# RocketWatch-BOTTOM.net
KiCad netlist of a schematic drawn in EAGLE
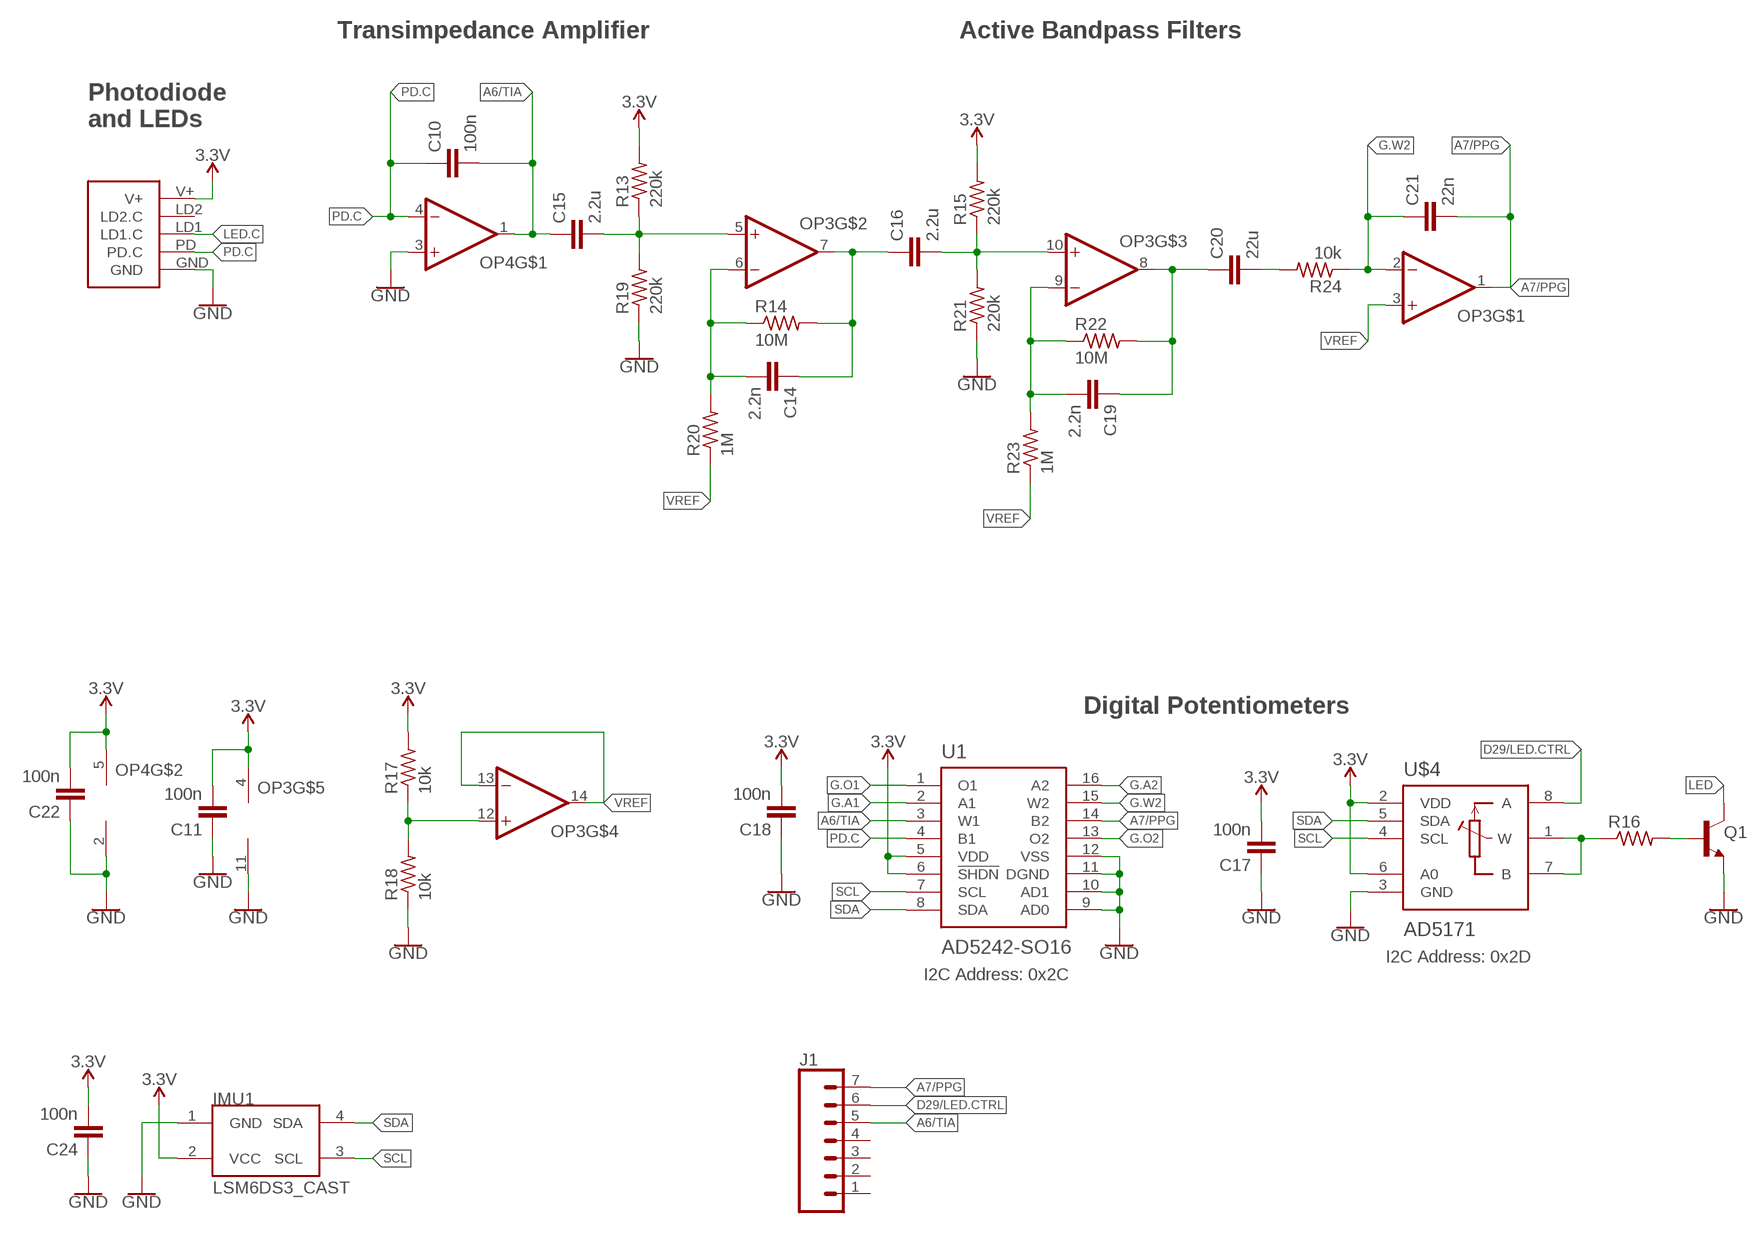
[diagram p0: schematic, sheet 1]

(export (version "E")
  (design (tool "Eeschema 10.0.6"))
  (components
    (comp (ref "C10")
      (value "100n")
      (footprint "eagle-import:C0603")
      (libsource (lib "eagle-import") (part "CAPACITOR0603"))
    )
    (comp (ref "C11")
      (value "100n")
      (footprint "eagle-import:C0603")
      (libsource (lib "eagle-import") (part "CAPACITOR0603"))
    )
    (comp (ref "C14")
      (value "2.2n")
      (footprint "eagle-import:C0603")
      (libsource (lib "eagle-import") (part "CAPACITOR0603"))
    )
    (comp (ref "C15")
      (value "2.2u")
      (footprint "eagle-import:C0603")
      (libsource (lib "eagle-import") (part "CAPACITOR0603"))
    )
    (comp (ref "C16")
      (value "2.2u")
      (footprint "eagle-import:C0603")
      (libsource (lib "eagle-import") (part "CAPACITOR0603"))
    )
    (comp (ref "C17")
      (value "100n")
      (footprint "eagle-import:C0603")
      (libsource (lib "eagle-import") (part "CAPACITOR0603"))
    )
    (comp (ref "C18")
      (value "100n")
      (footprint "eagle-import:C0603")
      (libsource (lib "eagle-import") (part "CAPACITOR0603"))
    )
    (comp (ref "C19")
      (value "2.2n")
      (footprint "eagle-import:C0603")
      (libsource (lib "eagle-import") (part "CAPACITOR0603"))
    )
    (comp (ref "C20")
      (value "22u")
      (footprint "eagle-import:C0603")
      (libsource (lib "eagle-import") (part "CAPACITOR0603"))
    )
    (comp (ref "C21")
      (value "22n")
      (footprint "eagle-import:C0603")
      (libsource (lib "eagle-import") (part "CAPACITOR0603"))
    )
    (comp (ref "C22")
      (value "100n")
      (footprint "eagle-import:C0603")
      (libsource (lib "eagle-import") (part "CAPACITOR0603"))
    )
    (comp (ref "C24")
      (value "100n")
      (footprint "eagle-import:C0603")
      (libsource (lib "eagle-import") (part "CAPACITOR0603"))
    )
    (comp (ref "IMU1")
      (value "LSM6DS3_CAST")
      (footprint "eagle-import:LSM6DS3_CAST")
      (libsource (lib "eagle-import") (part "LSM6DS3_CAST"))
    )
    (comp (ref "J1")
      (value "CONN_07")
      (footprint "eagle-import:1X07")
      (libsource (lib "eagle-import") (part "CONN_07"))
    )
    (comp (ref "OP3")
      (value "OP-QUAD-SO14")
      (footprint "eagle-import:SO14")
      (libsource (lib "eagle-import") (part "OP-QUAD-SO14"))
    )
    (comp (ref "OP4")
      (value "OP-SINGLEOT")
      (footprint "eagle-import:SOT23-5")
      (libsource (lib "eagle-import") (part "OP-SINGLEOT"))
    )
    (comp (ref "Q1")
      (value "NPN-GENERIC")
      (footprint "eagle-import:SOT23-3")
      (libsource (lib "eagle-import") (part "NPN-GENERIC"))
    )
    (comp (ref "R13")
      (value "220k")
      (footprint "eagle-import:R0603")
      (libsource (lib "eagle-import") (part "RESISTOR0603"))
    )
    (comp (ref "R14")
      (value "10M")
      (footprint "eagle-import:R0603")
      (libsource (lib "eagle-import") (part "RESISTOR0603"))
    )
    (comp (ref "R15")
      (value "220k")
      (footprint "eagle-import:R0603")
      (libsource (lib "eagle-import") (part "RESISTOR0603"))
    )
    (comp (ref "R16")
      (value "RESISTOR0603")
      (footprint "eagle-import:R0603")
      (libsource (lib "eagle-import") (part "RESISTOR0603"))
    )
    (comp (ref "R17")
      (value "10k")
      (footprint "eagle-import:R0402")
      (libsource (lib "eagle-import") (part "RESISTOR0402"))
    )
    (comp (ref "R18")
      (value "10k")
      (footprint "eagle-import:R0402")
      (libsource (lib "eagle-import") (part "RESISTOR0402"))
    )
    (comp (ref "R19")
      (value "220k")
      (footprint "eagle-import:R0603")
      (libsource (lib "eagle-import") (part "RESISTOR0603"))
    )
    (comp (ref "R20")
      (value "1M")
      (footprint "eagle-import:R0603")
      (libsource (lib "eagle-import") (part "RESISTOR0603"))
    )
    (comp (ref "R21")
      (value "220k")
      (footprint "eagle-import:R0603")
      (libsource (lib "eagle-import") (part "RESISTOR0603"))
    )
    (comp (ref "R22")
      (value "10M")
      (footprint "eagle-import:R0603")
      (libsource (lib "eagle-import") (part "RESISTOR0603"))
    )
    (comp (ref "R23")
      (value "1M")
      (footprint "eagle-import:R0603")
      (libsource (lib "eagle-import") (part "RESISTOR0603"))
    )
    (comp (ref "R24")
      (value "10k")
      (footprint "eagle-import:R0603")
      (libsource (lib "eagle-import") (part "RESISTOR0603"))
    )
    (comp (ref "U$3")
      (value "PPG.MODULE.2")
      (footprint "eagle-import:PPG.MODULE.2")
      (libsource (lib "eagle-import") (part "PPG.MODULE.2"))
    )
    (comp (ref "U$4")
      (value "AD5171")
      (footprint "eagle-import:SOT-23-8")
      (libsource (lib "eagle-import") (part "AD5171"))
    )
    (comp (ref "U1")
      (value "AD5242-SO16")
      (footprint "eagle-import:SO16")
      (libsource (lib "eagle-import") (part "AD5242-SO16"))
    )
  )
  (nets
    (net (code "1") (name "3.3V") (class "Default")
      (node (ref "C11") (pin "2") (pinfunction "2_2") (pintype "passive"))
      (node (ref "C17") (pin "2") (pinfunction "2_2") (pintype "passive"))
      (node (ref "C18") (pin "2") (pinfunction "2_2") (pintype "passive"))
      (node (ref "C22") (pin "2") (pinfunction "2_2") (pintype "passive"))
      (node (ref "C24") (pin "2") (pinfunction "2_2") (pintype "passive"))
      (node (ref "IMU1") (pin "2") (pinfunction "VCC_2") (pintype "bidirectional"))
      (node (ref "OP3") (pin "4") (pinfunction "V+_4") (pintype "power_in"))
      (node (ref "OP4") (pin "5") (pinfunction "V+_5") (pintype "power_in"))
      (node (ref "R13") (pin "2") (pinfunction "2_2") (pintype "passive"))
      (node (ref "R15") (pin "2") (pinfunction "2_2") (pintype "passive"))
      (node (ref "R17") (pin "2") (pinfunction "2_2") (pintype "passive"))
      (node (ref "U$3") (pin "V+") (pinfunction "V+_V+") (pintype "bidirectional"))
      (node (ref "U$4") (pin "2") (pinfunction "VDD_2") (pintype "bidirectional"))
      (node (ref "U$4") (pin "6") (pinfunction "A0_6") (pintype "bidirectional"))
      (node (ref "U1") (pin "5") (pinfunction "VDD_5") (pintype "bidirectional"))
      (node (ref "U1") (pin "6") (pinfunction "~{SHDN}_6") (pintype "bidirectional"))
    )
    (net (code "2") (name "A6{slash}TIA") (class "Default")
      (node (ref "C10") (pin "2") (pinfunction "2_2") (pintype "passive"))
      (node (ref "C15") (pin "1") (pinfunction "1_1") (pintype "passive"))
      (node (ref "J1") (pin "5") (pinfunction "5_5") (pintype "passive"))
      (node (ref "OP4") (pin "1") (pinfunction "OUT_1") (pintype "output"))
      (node (ref "U1") (pin "3") (pinfunction "W1_3") (pintype "bidirectional"))
    )
    (net (code "3") (name "A7{slash}PPG") (class "Default")
      (node (ref "C21") (pin "2") (pinfunction "2_2") (pintype "passive"))
      (node (ref "J1") (pin "7") (pinfunction "7_7") (pintype "passive"))
      (node (ref "OP3") (pin "1") (pinfunction "OUT_1") (pintype "output"))
      (node (ref "U1") (pin "14") (pinfunction "B2_14") (pintype "bidirectional"))
    )
    (net (code "4") (name "D29{slash}LED.CTRL") (class "Default")
      (node (ref "J1") (pin "6") (pinfunction "6_6") (pintype "passive"))
      (node (ref "U$4") (pin "8") (pinfunction "A_8") (pintype "bidirectional"))
    )
    (net (code "5") (name "G.A1") (class "Default")
      (node (ref "U1") (pin "2") (pinfunction "A1_2") (pintype "bidirectional"))
    )
    (net (code "6") (name "G.A2") (class "Default")
      (node (ref "U1") (pin "16") (pinfunction "A2_16") (pintype "bidirectional"))
    )
    (net (code "7") (name "G.O1") (class "Default")
      (node (ref "U1") (pin "1") (pinfunction "O1_1") (pintype "bidirectional"))
    )
    (net (code "8") (name "G.O2") (class "Default")
      (node (ref "U1") (pin "13") (pinfunction "O2_13") (pintype "bidirectional"))
    )
    (net (code "9") (name "G.W2") (class "Default")
      (node (ref "C21") (pin "1") (pinfunction "1_1") (pintype "passive"))
      (node (ref "OP3") (pin "2") (pinfunction "-IN_2") (pintype "input"))
      (node (ref "R24") (pin "1") (pinfunction "1_1") (pintype "passive"))
      (node (ref "U1") (pin "15") (pinfunction "W2_15") (pintype "bidirectional"))
    )
    (net (code "10") (name "GND") (class "Default")
      (node (ref "C11") (pin "1") (pinfunction "1_1") (pintype "passive"))
      (node (ref "C17") (pin "1") (pinfunction "1_1") (pintype "passive"))
      (node (ref "C18") (pin "1") (pinfunction "1_1") (pintype "passive"))
      (node (ref "C22") (pin "1") (pinfunction "1_1") (pintype "passive"))
      (node (ref "C24") (pin "1") (pinfunction "1_1") (pintype "passive"))
      (node (ref "IMU1") (pin "1") (pinfunction "GND_1") (pintype "bidirectional"))
      (node (ref "OP3") (pin "11") (pinfunction "V-_11") (pintype "power_in"))
      (node (ref "OP4") (pin "2") (pinfunction "V-_2") (pintype "power_in"))
      (node (ref "OP4") (pin "3") (pinfunction "+IN_3") (pintype "input"))
      (node (ref "Q1") (pin "2") (pinfunction "E_2") (pintype "passive"))
      (node (ref "R18") (pin "1") (pinfunction "1_1") (pintype "passive"))
      (node (ref "R19") (pin "1") (pinfunction "1_1") (pintype "passive"))
      (node (ref "R21") (pin "1") (pinfunction "1_1") (pintype "passive"))
      (node (ref "U$3") (pin "GND") (pinfunction "GND_GND") (pintype "bidirectional"))
      (node (ref "U$4") (pin "3") (pinfunction "GND_3") (pintype "bidirectional"))
      (node (ref "U1") (pin "10") (pinfunction "AD1_10") (pintype "bidirectional"))
      (node (ref "U1") (pin "11") (pinfunction "DGND_11") (pintype "bidirectional"))
      (node (ref "U1") (pin "12") (pinfunction "VSS_12") (pintype "bidirectional"))
      (node (ref "U1") (pin "9") (pinfunction "AD0_9") (pintype "bidirectional"))
    )
    (net (code "11") (name "LED") (class "Default")
      (node (ref "Q1") (pin "3") (pinfunction "C_3") (pintype "passive"))
    )
    (net (code "12") (name "LED.C") (class "Default")
      (node (ref "U$3") (pin "LD1") (pinfunction "LD1.C_LD1") (pintype "bidirectional"))
    )
    (net (code "13") (name "Net-(C20-Pad2)") (class "Default")
      (node (ref "C20") (pin "2") (pinfunction "2_2") (pintype "passive"))
      (node (ref "R24") (pin "2") (pinfunction "2_2") (pintype "passive"))
    )
    (net (code "14") (name "Net-(OP3B-+IN)") (class "Default")
      (node (ref "C15") (pin "2") (pinfunction "2_2") (pintype "passive"))
      (node (ref "OP3") (pin "5") (pinfunction "+IN_5") (pintype "input"))
      (node (ref "R13") (pin "1") (pinfunction "1_1") (pintype "passive"))
      (node (ref "R19") (pin "2") (pinfunction "2_2") (pintype "passive"))
    )
    (net (code "15") (name "Net-(OP3B--IN)") (class "Default")
      (node (ref "C14") (pin "2") (pinfunction "2_2") (pintype "passive"))
      (node (ref "OP3") (pin "6") (pinfunction "-IN_6") (pintype "input"))
      (node (ref "R14") (pin "1") (pinfunction "1_1") (pintype "passive"))
      (node (ref "R20") (pin "2") (pinfunction "2_2") (pintype "passive"))
    )
    (net (code "16") (name "Net-(OP3B-OUT)") (class "Default")
      (node (ref "C14") (pin "1") (pinfunction "1_1") (pintype "passive"))
      (node (ref "C16") (pin "1") (pinfunction "1_1") (pintype "passive"))
      (node (ref "OP3") (pin "7") (pinfunction "OUT_7") (pintype "output"))
      (node (ref "R14") (pin "2") (pinfunction "2_2") (pintype "passive"))
    )
    (net (code "17") (name "Net-(OP3C-+IN)") (class "Default")
      (node (ref "C16") (pin "2") (pinfunction "2_2") (pintype "passive"))
      (node (ref "OP3") (pin "10") (pinfunction "+IN_10") (pintype "input"))
      (node (ref "R15") (pin "1") (pinfunction "1_1") (pintype "passive"))
      (node (ref "R21") (pin "2") (pinfunction "2_2") (pintype "passive"))
    )
    (net (code "18") (name "Net-(OP3C--IN)") (class "Default")
      (node (ref "C19") (pin "2") (pinfunction "2_2") (pintype "passive"))
      (node (ref "OP3") (pin "9") (pinfunction "-IN_9") (pintype "input"))
      (node (ref "R22") (pin "1") (pinfunction "1_1") (pintype "passive"))
      (node (ref "R23") (pin "2") (pinfunction "2_2") (pintype "passive"))
    )
    (net (code "19") (name "Net-(OP3C-OUT)") (class "Default")
      (node (ref "C19") (pin "1") (pinfunction "1_1") (pintype "passive"))
      (node (ref "C20") (pin "1") (pinfunction "1_1") (pintype "passive"))
      (node (ref "OP3") (pin "8") (pinfunction "OUT_8") (pintype "output"))
      (node (ref "R22") (pin "2") (pinfunction "2_2") (pintype "passive"))
    )
    (net (code "20") (name "Net-(OP3D-+IN)") (class "Default")
      (node (ref "OP3") (pin "12") (pinfunction "+IN_12") (pintype "input"))
      (node (ref "R17") (pin "1") (pinfunction "1_1") (pintype "passive"))
      (node (ref "R18") (pin "2") (pinfunction "2_2") (pintype "passive"))
    )
    (net (code "21") (name "Net-(Q1-B)") (class "Default")
      (node (ref "Q1") (pin "1") (pinfunction "B_1") (pintype "passive"))
      (node (ref "R16") (pin "2") (pinfunction "2_2") (pintype "passive"))
    )
    (net (code "22") (name "Net-(U$4-B)") (class "Default")
      (node (ref "R16") (pin "1") (pinfunction "1_1") (pintype "passive"))
      (node (ref "U$4") (pin "1") (pinfunction "W_1") (pintype "bidirectional"))
      (node (ref "U$4") (pin "7") (pinfunction "B_7") (pintype "bidirectional"))
    )
    (net (code "23") (name "PD.C") (class "Default")
      (node (ref "C10") (pin "1") (pinfunction "1_1") (pintype "passive"))
      (node (ref "OP4") (pin "4") (pinfunction "-IN_4") (pintype "input"))
      (node (ref "U$3") (pin "PD") (pinfunction "PD.C_PD") (pintype "bidirectional"))
      (node (ref "U1") (pin "4") (pinfunction "B1_4") (pintype "bidirectional"))
    )
    (net (code "24") (name "SCL") (class "Default")
      (node (ref "IMU1") (pin "3") (pinfunction "SCL_3") (pintype "bidirectional"))
      (node (ref "U$4") (pin "4") (pinfunction "SCL_4") (pintype "bidirectional"))
      (node (ref "U1") (pin "7") (pinfunction "SCL_7") (pintype "bidirectional"))
    )
    (net (code "25") (name "SDA") (class "Default")
      (node (ref "IMU1") (pin "4") (pinfunction "SDA_4") (pintype "bidirectional"))
      (node (ref "U$4") (pin "5") (pinfunction "SDA_5") (pintype "bidirectional"))
      (node (ref "U1") (pin "8") (pinfunction "SDA_8") (pintype "bidirectional"))
    )
    (net (code "26") (name "VREF") (class "Default")
      (node (ref "OP3") (pin "13") (pinfunction "-IN_13") (pintype "input"))
      (node (ref "OP3") (pin "14") (pinfunction "OUT_14") (pintype "output"))
      (node (ref "OP3") (pin "3") (pinfunction "+IN_3") (pintype "input"))
      (node (ref "R20") (pin "1") (pinfunction "1_1") (pintype "passive"))
      (node (ref "R23") (pin "1") (pinfunction "1_1") (pintype "passive"))
    )
    (net (code "27") (name "unconnected-(J1-Pad1)") (class "Default")
      (node (ref "J1") (pin "1") (pinfunction "1_1") (pintype "passive"))
    )
    (net (code "28") (name "unconnected-(J1-Pad2)") (class "Default")
      (node (ref "J1") (pin "2") (pinfunction "2_2") (pintype "passive"))
    )
    (net (code "29") (name "unconnected-(J1-Pad3)") (class "Default")
      (node (ref "J1") (pin "3") (pinfunction "3_3") (pintype "passive"))
    )
    (net (code "30") (name "unconnected-(J1-Pad4)") (class "Default")
      (node (ref "J1") (pin "4") (pinfunction "4_4") (pintype "passive"))
    )
    (net (code "31") (name "unconnected-(U$3-LD2.C-PadLD2)") (class "Default")
      (node (ref "U$3") (pin "LD2") (pinfunction "LD2.C_LD2") (pintype "bidirectional"))
    )
  )
)
